# StandUp.net
KiCad netlist of a schematic drawn in EAGLE
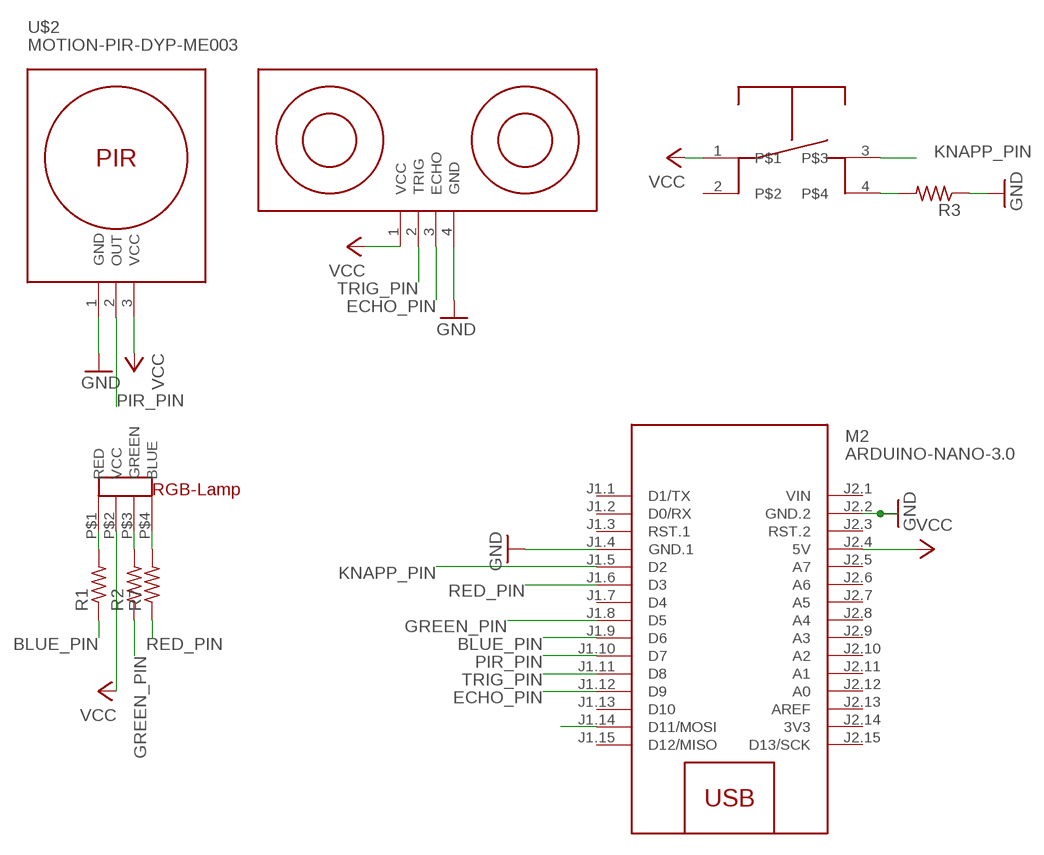
[diagram p0: schematic, sheet 1]

(export (version "E")
  (design (tool "Eeschema 10.0.6"))
  (components
    (comp (ref "M2")
      (value "ARDUINO-NANO-3.0")
      (footprint "eagle-import:ARDUINO-NANO-3.0")
      (libsource (lib "eagle-import") (part "ARDUINO-NANO-3.0"))
    )
    (comp (ref "R1")
      (value "R-US_0204/7")
      (footprint "eagle-import:0204_7")
      (libsource (lib "eagle-import") (part "R-US_0204/7"))
    )
    (comp (ref "R2")
      (value "R-US_0204/7")
      (footprint "eagle-import:0204_7")
      (libsource (lib "eagle-import") (part "R-US_0204/7"))
    )
    (comp (ref "R3")
      (value "R-US_0204/7")
      (footprint "eagle-import:0204_7")
      (libsource (lib "eagle-import") (part "R-US_0204/7"))
    )
    (comp (ref "R7")
      (value "R-US_0204/7")
      (footprint "eagle-import:0204_7")
      (libsource (lib "eagle-import") (part "R-US_0204/7"))
    )
    (comp (ref "U$2")
      (value "MOTION-PIR-DYP-ME003")
      (footprint "eagle-import:MOTION-PIR-DYP-ME003")
      (libsource (lib "eagle-import") (part "MOTION-PIR-DYP-ME003"))
    )
    (comp (ref "U$3")
      (value "ULTRASONIC-HC-SR04#V")
      (footprint "eagle-import:ULTRASONIC-HC-SR04#V")
      (libsource (lib "eagle-import") (part "ULTRASONIC-HC-SR04#V"))
    )
    (comp (ref "U$4")
      (value "KNAPP-TSA")
      (footprint "eagle-import:KNAPP-TSA")
      (libsource (lib "eagle-import") (part "KNAPP-TSA"))
    )
    (comp (ref "U$5")
      (value "RGBLAMP")
      (footprint "eagle-import:RGBLAMP")
      (libsource (lib "eagle-import") (part "RGBLAMP"))
    )
  )
  (nets
    (net (code "1") (name "/3V3") (class "Default")
      (node (ref "M2") (pin "J2.14") (pinfunction "3V3_J2.14") (pintype "power_in"))
    )
    (net (code "2") (name "/BLUE_PIN") (class "Default")
      (node (ref "M2") (pin "J1.9") (pinfunction "D6_J1.9") (pintype "bidirectional"))
      (node (ref "R1") (pin "1") (pinfunction "1_1") (pintype "passive"))
    )
    (net (code "3") (name "/ECHO_PIN") (class "Default")
      (node (ref "M2") (pin "J1.12") (pinfunction "D9_J1.12") (pintype "bidirectional"))
      (node (ref "U$3") (pin "3") (pinfunction "ECHO_3") (pintype "output"))
    )
    (net (code "4") (name "/GREEN_PIN") (class "Default")
      (node (ref "M2") (pin "J1.8") (pinfunction "D5_J1.8") (pintype "bidirectional"))
      (node (ref "R2") (pin "1") (pinfunction "1_1") (pintype "passive"))
    )
    (net (code "5") (name "/KNAPP_PIN") (class "Default")
      (node (ref "M2") (pin "J1.5") (pinfunction "D2_J1.5") (pintype "bidirectional"))
      (node (ref "U$4") (pin "3") (pinfunction "P$3_3") (pintype "bidirectional"))
    )
    (net (code "6") (name "/PIR_PIN") (class "Default")
      (node (ref "M2") (pin "J1.10") (pinfunction "D7_J1.10") (pintype "bidirectional"))
      (node (ref "U$2") (pin "2") (pinfunction "OUT_2") (pintype "output"))
    )
    (net (code "7") (name "/RED_PIN") (class "Default")
      (node (ref "M2") (pin "J1.6") (pinfunction "D3_J1.6") (pintype "bidirectional"))
      (node (ref "R7") (pin "1") (pinfunction "1_1") (pintype "passive"))
    )
    (net (code "8") (name "/TRIG_PIN") (class "Default")
      (node (ref "M2") (pin "J1.11") (pinfunction "D8_J1.11") (pintype "bidirectional"))
      (node (ref "U$3") (pin "2") (pinfunction "TRIG_2") (pintype "input"))
    )
    (net (code "9") (name "/VIN") (class "Default")
      (node (ref "M2") (pin "J2.1") (pinfunction "VIN_J2.1") (pintype "power_in"))
    )
    (net (code "10") (name "GND") (class "Default")
      (node (ref "M2") (pin "J1.4") (pinfunction "GND.1_J1.4") (pintype "power_in"))
      (node (ref "M2") (pin "J2.2") (pinfunction "GND.2_J2.2") (pintype "power_in"))
      (node (ref "R3") (pin "1") (pinfunction "1_1") (pintype "passive"))
      (node (ref "U$2") (pin "1") (pinfunction "GND_1") (pintype "power_in"))
      (node (ref "U$3") (pin "4") (pinfunction "GND_4") (pintype "power_in"))
    )
    (net (code "11") (name "Net-(U$4-P$4)") (class "Default")
      (node (ref "R3") (pin "2") (pinfunction "2_2") (pintype "passive"))
      (node (ref "U$4") (pin "4") (pinfunction "P$4_4") (pintype "bidirectional"))
    )
    (net (code "12") (name "Net-(U$5-BLUE)") (class "Default")
      (node (ref "R7") (pin "2") (pinfunction "2_2") (pintype "passive"))
      (node (ref "U$5") (pin "P$4") (pinfunction "BLUE_P$4") (pintype "bidirectional"))
    )
    (net (code "13") (name "Net-(U$5-GREEN)") (class "Default")
      (node (ref "R2") (pin "2") (pinfunction "2_2") (pintype "passive"))
      (node (ref "U$5") (pin "P$3") (pinfunction "GREEN_P$3") (pintype "bidirectional"))
    )
    (net (code "14") (name "Net-(U$5-RED)") (class "Default")
      (node (ref "R1") (pin "2") (pinfunction "2_2") (pintype "passive"))
      (node (ref "U$5") (pin "P$1") (pinfunction "RED_P$1") (pintype "bidirectional"))
    )
    (net (code "15") (name "VCC") (class "Default")
      (node (ref "M2") (pin "J2.4") (pinfunction "5V_J2.4") (pintype "power_in"))
      (node (ref "U$2") (pin "3") (pinfunction "VCC_3") (pintype "power_in"))
      (node (ref "U$3") (pin "1") (pinfunction "VCC_1") (pintype "power_in"))
      (node (ref "U$4") (pin "1") (pinfunction "P$1_1") (pintype "bidirectional"))
      (node (ref "U$5") (pin "P$2") (pinfunction "VCC_P$2") (pintype "bidirectional"))
    )
    (net (code "16") (name "unconnected-(M2-A0-PadJ2.12)") (class "Default")
      (node (ref "M2") (pin "J2.12") (pinfunction "A0_J2.12") (pintype "bidirectional"))
    )
    (net (code "17") (name "unconnected-(M2-A1-PadJ2.11)") (class "Default")
      (node (ref "M2") (pin "J2.11") (pinfunction "A1_J2.11") (pintype "bidirectional"))
    )
    (net (code "18") (name "unconnected-(M2-A2-PadJ2.10)") (class "Default")
      (node (ref "M2") (pin "J2.10") (pinfunction "A2_J2.10") (pintype "bidirectional"))
    )
    (net (code "19") (name "unconnected-(M2-A3-PadJ2.9)") (class "Default")
      (node (ref "M2") (pin "J2.9") (pinfunction "A3_J2.9") (pintype "bidirectional"))
    )
    (net (code "20") (name "unconnected-(M2-A4-PadJ2.8)") (class "Default")
      (node (ref "M2") (pin "J2.8") (pinfunction "A4_J2.8") (pintype "bidirectional"))
    )
    (net (code "21") (name "unconnected-(M2-A5-PadJ2.7)") (class "Default")
      (node (ref "M2") (pin "J2.7") (pinfunction "A5_J2.7") (pintype "bidirectional"))
    )
    (net (code "22") (name "unconnected-(M2-A6-PadJ2.6)") (class "Default")
      (node (ref "M2") (pin "J2.6") (pinfunction "A6_J2.6") (pintype "bidirectional"))
    )
    (net (code "23") (name "unconnected-(M2-A7-PadJ2.5)") (class "Default")
      (node (ref "M2") (pin "J2.5") (pinfunction "A7_J2.5") (pintype "bidirectional"))
    )
    (net (code "24") (name "unconnected-(M2-AREF-PadJ2.13)") (class "Default")
      (node (ref "M2") (pin "J2.13") (pinfunction "AREF_J2.13") (pintype "bidirectional"))
    )
    (net (code "25") (name "unconnected-(M2-D0{slash}RX-PadJ1.2)") (class "Default")
      (node (ref "M2") (pin "J1.2") (pinfunction "D0/RX_J1.2") (pintype "bidirectional"))
    )
    (net (code "26") (name "unconnected-(M2-D1{slash}TX-PadJ1.1)") (class "Default")
      (node (ref "M2") (pin "J1.1") (pinfunction "D1/TX_J1.1") (pintype "bidirectional"))
    )
    (net (code "27") (name "unconnected-(M2-D4-PadJ1.7)") (class "Default")
      (node (ref "M2") (pin "J1.7") (pinfunction "D4_J1.7") (pintype "bidirectional"))
    )
    (net (code "28") (name "unconnected-(M2-D10-PadJ1.13)") (class "Default")
      (node (ref "M2") (pin "J1.13") (pinfunction "D10_J1.13") (pintype "bidirectional"))
    )
    (net (code "29") (name "unconnected-(M2-D11{slash}MOSI-PadJ1.14)") (class "Default")
      (node (ref "M2") (pin "J1.14") (pinfunction "D11/MOSI_J1.14") (pintype "bidirectional"))
    )
    (net (code "30") (name "unconnected-(M2-D12{slash}MISO-PadJ1.15)") (class "Default")
      (node (ref "M2") (pin "J1.15") (pinfunction "D12/MISO_J1.15") (pintype "bidirectional"))
    )
    (net (code "31") (name "unconnected-(M2-D13{slash}SCK-PadJ2.15)") (class "Default")
      (node (ref "M2") (pin "J2.15") (pinfunction "D13/SCK_J2.15") (pintype "bidirectional"))
    )
    (net (code "32") (name "unconnected-(M2-RST.1-PadJ1.3)") (class "Default")
      (node (ref "M2") (pin "J1.3") (pinfunction "RST.1_J1.3") (pintype "bidirectional"))
    )
    (net (code "33") (name "unconnected-(M2-RST.2-PadJ2.3)") (class "Default")
      (node (ref "M2") (pin "J2.3") (pinfunction "RST.2_J2.3") (pintype "bidirectional"))
    )
    (net (code "34") (name "unconnected-(U$4-P$2-Pad2)") (class "Default")
      (node (ref "U$4") (pin "2") (pinfunction "P$2_2") (pintype "bidirectional"))
    )
  )
)
